# sensors.net
KiCad netlist of a schematic drawn in EAGLE
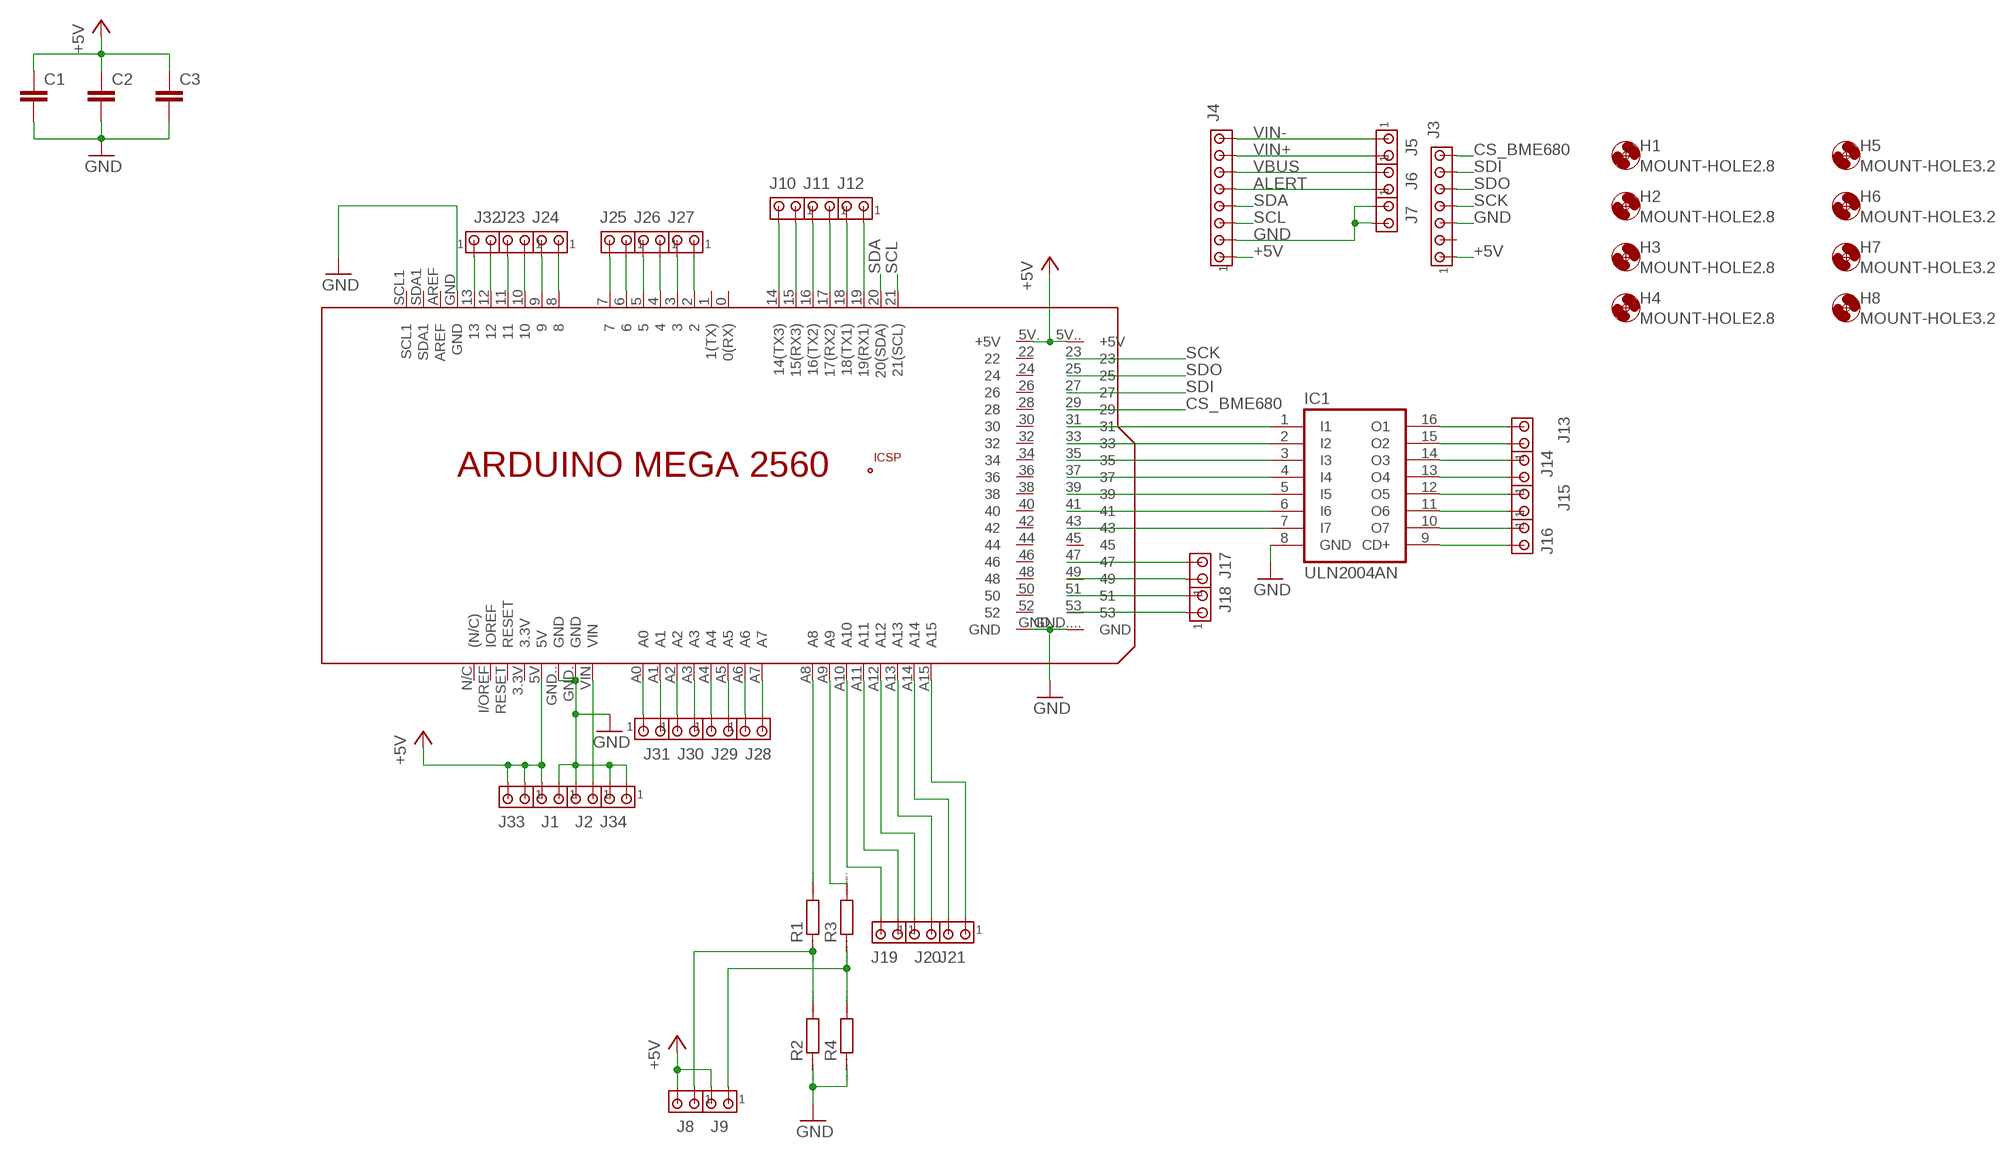
[diagram p0: schematic, sheet 1]

(export (version "E")
  (design (tool "Eeschema 10.0.6"))
  (components
    (comp (ref "C1")
      (value "C2,5-3")
      (footprint "eagle-import:C2.5-3")
      (libsource (lib "eagle-import") (part "C2,5-3"))
    )
    (comp (ref "C2")
      (value "C2,5-3")
      (footprint "eagle-import:C2.5-3")
      (libsource (lib "eagle-import") (part "C2,5-3"))
    )
    (comp (ref "C3")
      (value "C2,5-3")
      (footprint "eagle-import:C2.5-3")
      (libsource (lib "eagle-import") (part "C2,5-3"))
    )
    (comp (ref "H1")
      (value "MOUNT-HOLE2.8")
      (footprint "eagle-import:2,8")
      (libsource (lib "eagle-import") (part "MOUNT-HOLE2.8"))
    )
    (comp (ref "H2")
      (value "MOUNT-HOLE2.8")
      (footprint "eagle-import:2,8")
      (libsource (lib "eagle-import") (part "MOUNT-HOLE2.8"))
    )
    (comp (ref "H3")
      (value "MOUNT-HOLE2.8")
      (footprint "eagle-import:2,8")
      (libsource (lib "eagle-import") (part "MOUNT-HOLE2.8"))
    )
    (comp (ref "H4")
      (value "MOUNT-HOLE2.8")
      (footprint "eagle-import:2,8")
      (libsource (lib "eagle-import") (part "MOUNT-HOLE2.8"))
    )
    (comp (ref "H5")
      (value "MOUNT-HOLE3.2")
      (footprint "eagle-import:3,2")
      (libsource (lib "eagle-import") (part "MOUNT-HOLE3.2"))
    )
    (comp (ref "H6")
      (value "MOUNT-HOLE3.2")
      (footprint "eagle-import:3,2")
      (libsource (lib "eagle-import") (part "MOUNT-HOLE3.2"))
    )
    (comp (ref "H7")
      (value "MOUNT-HOLE3.2")
      (footprint "eagle-import:3,2")
      (libsource (lib "eagle-import") (part "MOUNT-HOLE3.2"))
    )
    (comp (ref "H8")
      (value "MOUNT-HOLE3.2")
      (footprint "eagle-import:3,2")
      (libsource (lib "eagle-import") (part "MOUNT-HOLE3.2"))
    )
    (comp (ref "IC1")
      (value "ULN2004AN")
      (footprint "eagle-import:DIL16")
      (libsource (lib "eagle-import") (part "ULN2004AN"))
    )
    (comp (ref "J1")
      (value "SCREW-2")
      (footprint "eagle-import:SCREW-2")
      (libsource (lib "eagle-import") (part "SCREW-2"))
    )
    (comp (ref "J2")
      (value "SCREW-2")
      (footprint "eagle-import:SCREW-2")
      (libsource (lib "eagle-import") (part "SCREW-2"))
    )
    (comp (ref "J3")
      (value "MTA07-100")
      (footprint "eagle-import:10X07MTA")
      (libsource (lib "eagle-import") (part "MTA07-100"))
    )
    (comp (ref "J4")
      (value "MTA08-100")
      (footprint "eagle-import:10X08MTA")
      (libsource (lib "eagle-import") (part "MTA08-100"))
    )
    (comp (ref "J5")
      (value "SCREW-2")
      (footprint "eagle-import:SCREW-2")
      (libsource (lib "eagle-import") (part "SCREW-2"))
    )
    (comp (ref "J6")
      (value "SCREW-2")
      (footprint "eagle-import:SCREW-2")
      (libsource (lib "eagle-import") (part "SCREW-2"))
    )
    (comp (ref "J7")
      (value "SCREW-2")
      (footprint "eagle-import:SCREW-2")
      (libsource (lib "eagle-import") (part "SCREW-2"))
    )
    (comp (ref "J8")
      (value "SCREW-2")
      (footprint "eagle-import:SCREW-2")
      (libsource (lib "eagle-import") (part "SCREW-2"))
    )
    (comp (ref "J9")
      (value "SCREW-2")
      (footprint "eagle-import:SCREW-2")
      (libsource (lib "eagle-import") (part "SCREW-2"))
    )
    (comp (ref "J10")
      (value "SCREW-2")
      (footprint "eagle-import:SCREW-2")
      (libsource (lib "eagle-import") (part "SCREW-2"))
    )
    (comp (ref "J11")
      (value "SCREW-2")
      (footprint "eagle-import:SCREW-2")
      (libsource (lib "eagle-import") (part "SCREW-2"))
    )
    (comp (ref "J12")
      (value "SCREW-2")
      (footprint "eagle-import:SCREW-2")
      (libsource (lib "eagle-import") (part "SCREW-2"))
    )
    (comp (ref "J13")
      (value "SCREW-2")
      (footprint "eagle-import:SCREW-2")
      (libsource (lib "eagle-import") (part "SCREW-2"))
    )
    (comp (ref "J14")
      (value "SCREW-2")
      (footprint "eagle-import:SCREW-2")
      (libsource (lib "eagle-import") (part "SCREW-2"))
    )
    (comp (ref "J15")
      (value "SCREW-2")
      (footprint "eagle-import:SCREW-2")
      (libsource (lib "eagle-import") (part "SCREW-2"))
    )
    (comp (ref "J16")
      (value "SCREW-2")
      (footprint "eagle-import:SCREW-2")
      (libsource (lib "eagle-import") (part "SCREW-2"))
    )
    (comp (ref "J17")
      (value "SCREW-2")
      (footprint "eagle-import:SCREW-2")
      (libsource (lib "eagle-import") (part "SCREW-2"))
    )
    (comp (ref "J18")
      (value "SCREW-2")
      (footprint "eagle-import:SCREW-2")
      (libsource (lib "eagle-import") (part "SCREW-2"))
    )
    (comp (ref "J19")
      (value "SCREW-2")
      (footprint "eagle-import:SCREW-2")
      (libsource (lib "eagle-import") (part "SCREW-2"))
    )
    (comp (ref "J20")
      (value "SCREW-2")
      (footprint "eagle-import:SCREW-2")
      (libsource (lib "eagle-import") (part "SCREW-2"))
    )
    (comp (ref "J21")
      (value "SCREW-2")
      (footprint "eagle-import:SCREW-2")
      (libsource (lib "eagle-import") (part "SCREW-2"))
    )
    (comp (ref "J23")
      (value "SCREW-2")
      (footprint "eagle-import:SCREW-2")
      (libsource (lib "eagle-import") (part "SCREW-2"))
    )
    (comp (ref "J24")
      (value "SCREW-2")
      (footprint "eagle-import:SCREW-2")
      (libsource (lib "eagle-import") (part "SCREW-2"))
    )
    (comp (ref "J25")
      (value "SCREW-2")
      (footprint "eagle-import:SCREW-2")
      (libsource (lib "eagle-import") (part "SCREW-2"))
    )
    (comp (ref "J26")
      (value "SCREW-2")
      (footprint "eagle-import:SCREW-2")
      (libsource (lib "eagle-import") (part "SCREW-2"))
    )
    (comp (ref "J27")
      (value "SCREW-2")
      (footprint "eagle-import:SCREW-2")
      (libsource (lib "eagle-import") (part "SCREW-2"))
    )
    (comp (ref "J28")
      (value "SCREW-2")
      (footprint "eagle-import:SCREW-2")
      (libsource (lib "eagle-import") (part "SCREW-2"))
    )
    (comp (ref "J29")
      (value "SCREW-2")
      (footprint "eagle-import:SCREW-2")
      (libsource (lib "eagle-import") (part "SCREW-2"))
    )
    (comp (ref "J30")
      (value "SCREW-2")
      (footprint "eagle-import:SCREW-2")
      (libsource (lib "eagle-import") (part "SCREW-2"))
    )
    (comp (ref "J31")
      (value "SCREW-2")
      (footprint "eagle-import:SCREW-2")
      (libsource (lib "eagle-import") (part "SCREW-2"))
    )
    (comp (ref "J32")
      (value "SCREW-2")
      (footprint "eagle-import:SCREW-2")
      (libsource (lib "eagle-import") (part "SCREW-2"))
    )
    (comp (ref "J33")
      (value "SCREW-2")
      (footprint "eagle-import:SCREW-2")
      (libsource (lib "eagle-import") (part "SCREW-2"))
    )
    (comp (ref "J34")
      (value "SCREW-2")
      (footprint "eagle-import:SCREW-2")
      (libsource (lib "eagle-import") (part "SCREW-2"))
    )
    (comp (ref "PCB1")
      (value "ARDUINO_MEGA2560_NEW")
      (footprint "eagle-import:ARDUINO_MEGA2560")
      (libsource (lib "eagle-import") (part "ARDUINO_MEGA2560_NEW"))
    )
    (comp (ref "R1")
      (value "R0207/10")
      (footprint "eagle-import:0207_10")
      (libsource (lib "eagle-import") (part "R0207/10"))
    )
    (comp (ref "R2")
      (value "R0207/10")
      (footprint "eagle-import:0207_10")
      (libsource (lib "eagle-import") (part "R0207/10"))
    )
    (comp (ref "R3")
      (value "R0207/10")
      (footprint "eagle-import:0207_10")
      (libsource (lib "eagle-import") (part "R0207/10"))
    )
    (comp (ref "R4")
      (value "R0207/10")
      (footprint "eagle-import:0207_10")
      (libsource (lib "eagle-import") (part "R0207/10"))
    )
  )
  (nets
    (net (code "1") (name "+5V") (class "Default")
      (node (ref "C1") (pin "1") (pinfunction "1_1") (pintype "passive"))
      (node (ref "C2") (pin "1") (pinfunction "1_1") (pintype "passive"))
      (node (ref "C3") (pin "1") (pinfunction "1_1") (pintype "passive"))
      (node (ref "J1") (pin "2") (pinfunction "2_2") (pintype "passive"))
      (node (ref "J3") (pin "1") (pinfunction "1_1") (pintype "passive"))
      (node (ref "J33") (pin "1") (pinfunction "1_1") (pintype "passive"))
      (node (ref "J33") (pin "2") (pinfunction "2_2") (pintype "passive"))
      (node (ref "J4") (pin "1") (pinfunction "1_1") (pintype "passive"))
      (node (ref "J8") (pin "2") (pinfunction "2_2") (pintype "passive"))
      (node (ref "J9") (pin "2") (pinfunction "2_2") (pintype "passive"))
      (node (ref "PCB1") (pin "5V") (pinfunction "5V_5V") (pintype "bidirectional"))
      (node (ref "PCB1") (pin "5V.") (pinfunction "+5V_5V.") (pintype "bidirectional"))
      (node (ref "PCB1") (pin "5V..") (pinfunction "+5V_5V..") (pintype "bidirectional"))
    )
    (net (code "2") (name "/ALERT") (class "Default")
      (node (ref "J4") (pin "5") (pinfunction "5_5") (pintype "passive"))
      (node (ref "J6") (pin "2") (pinfunction "2_2") (pintype "passive"))
    )
    (net (code "3") (name "/CS_BME680") (class "Default")
      (node (ref "J3") (pin "7") (pinfunction "7_7") (pintype "passive"))
      (node (ref "PCB1") (pin "29") (pinfunction "29_29") (pintype "bidirectional"))
    )
    (net (code "4") (name "/SCK") (class "Default")
      (node (ref "J3") (pin "4") (pinfunction "4_4") (pintype "passive"))
      (node (ref "PCB1") (pin "23") (pinfunction "23_23") (pintype "bidirectional"))
    )
    (net (code "5") (name "/SCL") (class "Default")
      (node (ref "J4") (pin "3") (pinfunction "3_3") (pintype "passive"))
      (node (ref "PCB1") (pin "21") (pinfunction "21(SCL)_21") (pintype "bidirectional"))
    )
    (net (code "6") (name "/SDA") (class "Default")
      (node (ref "J4") (pin "4") (pinfunction "4_4") (pintype "passive"))
      (node (ref "PCB1") (pin "20") (pinfunction "20(SDA)_20") (pintype "bidirectional"))
    )
    (net (code "7") (name "/SDI") (class "Default")
      (node (ref "J3") (pin "6") (pinfunction "6_6") (pintype "passive"))
      (node (ref "PCB1") (pin "27") (pinfunction "27_27") (pintype "bidirectional"))
    )
    (net (code "8") (name "/SDO") (class "Default")
      (node (ref "J3") (pin "5") (pinfunction "5_5") (pintype "passive"))
      (node (ref "PCB1") (pin "25") (pinfunction "25_25") (pintype "bidirectional"))
    )
    (net (code "9") (name "/VBUS") (class "Default")
      (node (ref "J4") (pin "6") (pinfunction "6_6") (pintype "passive"))
      (node (ref "J6") (pin "1") (pinfunction "1_1") (pintype "passive"))
    )
    (net (code "10") (name "/VIN+") (class "Default")
      (node (ref "J4") (pin "7") (pinfunction "7_7") (pintype "passive"))
      (node (ref "J5") (pin "2") (pinfunction "2_2") (pintype "passive"))
    )
    (net (code "11") (name "/VIN-") (class "Default")
      (node (ref "J4") (pin "8") (pinfunction "8_8") (pintype "passive"))
      (node (ref "J5") (pin "1") (pinfunction "1_1") (pintype "passive"))
    )
    (net (code "12") (name "GND") (class "Default")
      (node (ref "C1") (pin "2") (pinfunction "2_2") (pintype "passive"))
      (node (ref "C2") (pin "2") (pinfunction "2_2") (pintype "passive"))
      (node (ref "C3") (pin "2") (pinfunction "2_2") (pintype "passive"))
      (node (ref "IC1") (pin "8") (pinfunction "GND_8") (pintype "power_in"))
      (node (ref "J1") (pin "1") (pinfunction "1_1") (pintype "passive"))
      (node (ref "J2") (pin "2") (pinfunction "2_2") (pintype "passive"))
      (node (ref "J3") (pin "3") (pinfunction "3_3") (pintype "passive"))
      (node (ref "J34") (pin "1") (pinfunction "1_1") (pintype "passive"))
      (node (ref "J34") (pin "2") (pinfunction "2_2") (pintype "passive"))
      (node (ref "J4") (pin "2") (pinfunction "2_2") (pintype "passive"))
      (node (ref "J7") (pin "1") (pinfunction "1_1") (pintype "passive"))
      (node (ref "J7") (pin "2") (pinfunction "2_2") (pintype "passive"))
      (node (ref "PCB1") (pin "GND") (pinfunction "GND_GND") (pintype "bidirectional"))
      (node (ref "PCB1") (pin "GND.") (pinfunction "GND_GND.") (pintype "bidirectional"))
      (node (ref "PCB1") (pin "GND..") (pinfunction "GND_GND..") (pintype "bidirectional"))
      (node (ref "PCB1") (pin "GND...") (pinfunction "GND_GND...") (pintype "bidirectional"))
      (node (ref "PCB1") (pin "GND....") (pinfunction "GND_GND....") (pintype "bidirectional"))
      (node (ref "R2") (pin "1") (pinfunction "1_1") (pintype "passive"))
      (node (ref "R4") (pin "1") (pinfunction "1_1") (pintype "passive"))
    )
    (net (code "13") (name "Net-(IC1-CD+)") (class "Default")
      (node (ref "IC1") (pin "9") (pinfunction "CD+_9") (pintype "passive"))
      (node (ref "J16") (pin "2") (pinfunction "2_2") (pintype "passive"))
    )
    (net (code "14") (name "Net-(IC1-I1)") (class "Default")
      (node (ref "IC1") (pin "1") (pinfunction "I1_1") (pintype "input"))
      (node (ref "PCB1") (pin "31") (pinfunction "31_31") (pintype "bidirectional"))
    )
    (net (code "15") (name "Net-(IC1-I2)") (class "Default")
      (node (ref "IC1") (pin "2") (pinfunction "I2_2") (pintype "input"))
      (node (ref "PCB1") (pin "33") (pinfunction "33_33") (pintype "bidirectional"))
    )
    (net (code "16") (name "Net-(IC1-I3)") (class "Default")
      (node (ref "IC1") (pin "3") (pinfunction "I3_3") (pintype "input"))
      (node (ref "PCB1") (pin "35") (pinfunction "35_35") (pintype "bidirectional"))
    )
    (net (code "17") (name "Net-(IC1-I4)") (class "Default")
      (node (ref "IC1") (pin "4") (pinfunction "I4_4") (pintype "input"))
      (node (ref "PCB1") (pin "37") (pinfunction "37_37") (pintype "bidirectional"))
    )
    (net (code "18") (name "Net-(IC1-I5)") (class "Default")
      (node (ref "IC1") (pin "5") (pinfunction "I5_5") (pintype "input"))
      (node (ref "PCB1") (pin "39") (pinfunction "39_39") (pintype "bidirectional"))
    )
    (net (code "19") (name "Net-(IC1-I6)") (class "Default")
      (node (ref "IC1") (pin "6") (pinfunction "I6_6") (pintype "input"))
      (node (ref "PCB1") (pin "41") (pinfunction "41_41") (pintype "bidirectional"))
    )
    (net (code "20") (name "Net-(IC1-I7)") (class "Default")
      (node (ref "IC1") (pin "7") (pinfunction "I7_7") (pintype "input"))
      (node (ref "PCB1") (pin "43") (pinfunction "43_43") (pintype "bidirectional"))
    )
    (net (code "21") (name "Net-(IC1-O1)") (class "Default")
      (node (ref "IC1") (pin "16") (pinfunction "O1_16") (pintype "open_collector"))
      (node (ref "J13") (pin "2") (pinfunction "2_2") (pintype "passive"))
    )
    (net (code "22") (name "Net-(IC1-O2)") (class "Default")
      (node (ref "IC1") (pin "15") (pinfunction "O2_15") (pintype "open_collector"))
      (node (ref "J13") (pin "1") (pinfunction "1_1") (pintype "passive"))
    )
    (net (code "23") (name "Net-(IC1-O3)") (class "Default")
      (node (ref "IC1") (pin "14") (pinfunction "O3_14") (pintype "open_collector"))
      (node (ref "J14") (pin "2") (pinfunction "2_2") (pintype "passive"))
    )
    (net (code "24") (name "Net-(IC1-O4)") (class "Default")
      (node (ref "IC1") (pin "13") (pinfunction "O4_13") (pintype "open_collector"))
      (node (ref "J14") (pin "1") (pinfunction "1_1") (pintype "passive"))
    )
    (net (code "25") (name "Net-(IC1-O5)") (class "Default")
      (node (ref "IC1") (pin "12") (pinfunction "O5_12") (pintype "open_collector"))
      (node (ref "J15") (pin "2") (pinfunction "2_2") (pintype "passive"))
    )
    (net (code "26") (name "Net-(IC1-O6)") (class "Default")
      (node (ref "IC1") (pin "11") (pinfunction "O6_11") (pintype "open_collector"))
      (node (ref "J15") (pin "1") (pinfunction "1_1") (pintype "passive"))
    )
    (net (code "27") (name "Net-(IC1-O7)") (class "Default")
      (node (ref "IC1") (pin "10") (pinfunction "O7_10") (pintype "open_collector"))
      (node (ref "J16") (pin "1") (pinfunction "1_1") (pintype "passive"))
    )
    (net (code "28") (name "Net-(J2-Pad1)") (class "Default")
      (node (ref "J2") (pin "1") (pinfunction "1_1") (pintype "passive"))
      (node (ref "PCB1") (pin "VIN") (pinfunction "VIN_VIN") (pintype "bidirectional"))
    )
    (net (code "29") (name "Net-(J8-Pad1)") (class "Default")
      (node (ref "J8") (pin "1") (pinfunction "1_1") (pintype "passive"))
      (node (ref "R1") (pin "1") (pinfunction "1_1") (pintype "passive"))
      (node (ref "R2") (pin "2") (pinfunction "2_2") (pintype "passive"))
    )
    (net (code "30") (name "Net-(J9-Pad1)") (class "Default")
      (node (ref "J9") (pin "1") (pinfunction "1_1") (pintype "passive"))
      (node (ref "R3") (pin "1") (pinfunction "1_1") (pintype "passive"))
      (node (ref "R4") (pin "2") (pinfunction "2_2") (pintype "passive"))
    )
    (net (code "31") (name "Net-(J17-Pad1)") (class "Default")
      (node (ref "J17") (pin "1") (pinfunction "1_1") (pintype "passive"))
      (node (ref "PCB1") (pin "49") (pinfunction "49_49") (pintype "bidirectional"))
    )
    (net (code "32") (name "Net-(J17-Pad2)") (class "Default")
      (node (ref "J17") (pin "2") (pinfunction "2_2") (pintype "passive"))
      (node (ref "PCB1") (pin "47") (pinfunction "47_47") (pintype "bidirectional"))
    )
    (net (code "33") (name "Net-(J18-Pad1)") (class "Default")
      (node (ref "J18") (pin "1") (pinfunction "1_1") (pintype "passive"))
      (node (ref "PCB1") (pin "53") (pinfunction "53_53") (pintype "bidirectional"))
    )
    (net (code "34") (name "Net-(J18-Pad2)") (class "Default")
      (node (ref "J18") (pin "2") (pinfunction "2_2") (pintype "passive"))
      (node (ref "PCB1") (pin "51") (pinfunction "51_51") (pintype "bidirectional"))
    )
    (net (code "35") (name "Net-(J19-Pad1)") (class "Default")
      (node (ref "J19") (pin "1") (pinfunction "1_1") (pintype "passive"))
      (node (ref "PCB1") (pin "A11") (pinfunction "A11_A11") (pintype "bidirectional"))
    )
    (net (code "36") (name "Net-(J19-Pad2)") (class "Default")
      (node (ref "J19") (pin "2") (pinfunction "2_2") (pintype "passive"))
      (node (ref "PCB1") (pin "A10") (pinfunction "A10_A10") (pintype "bidirectional"))
    )
    (net (code "37") (name "Net-(J20-Pad1)") (class "Default")
      (node (ref "J20") (pin "1") (pinfunction "1_1") (pintype "passive"))
      (node (ref "PCB1") (pin "A12") (pinfunction "A12_A12") (pintype "bidirectional"))
    )
    (net (code "38") (name "Net-(J20-Pad2)") (class "Default")
      (node (ref "J20") (pin "2") (pinfunction "2_2") (pintype "passive"))
      (node (ref "PCB1") (pin "A13") (pinfunction "A13_A13") (pintype "bidirectional"))
    )
    (net (code "39") (name "Net-(J21-Pad1)") (class "Default")
      (node (ref "J21") (pin "1") (pinfunction "1_1") (pintype "passive"))
      (node (ref "PCB1") (pin "A15") (pinfunction "A15_A15") (pintype "bidirectional"))
    )
    (net (code "40") (name "Net-(J21-Pad2)") (class "Default")
      (node (ref "J21") (pin "2") (pinfunction "2_2") (pintype "passive"))
      (node (ref "PCB1") (pin "A14") (pinfunction "A14_A14") (pintype "bidirectional"))
    )
    (net (code "41") (name "Net-(J23-Pad1)") (class "Default")
      (node (ref "J23") (pin "1") (pinfunction "1_1") (pintype "passive"))
      (node (ref "PCB1") (pin "10") (pinfunction "10_10") (pintype "bidirectional"))
    )
    (net (code "42") (name "Net-(J23-Pad2)") (class "Default")
      (node (ref "J23") (pin "2") (pinfunction "2_2") (pintype "passive"))
      (node (ref "PCB1") (pin "11") (pinfunction "11_11") (pintype "bidirectional"))
    )
    (net (code "43") (name "Net-(J24-Pad1)") (class "Default")
      (node (ref "J24") (pin "1") (pinfunction "1_1") (pintype "passive"))
      (node (ref "PCB1") (pin "8") (pinfunction "8_8") (pintype "bidirectional"))
    )
    (net (code "44") (name "Net-(J24-Pad2)") (class "Default")
      (node (ref "J24") (pin "2") (pinfunction "2_2") (pintype "passive"))
      (node (ref "PCB1") (pin "9") (pinfunction "9_9") (pintype "bidirectional"))
    )
    (net (code "45") (name "Net-(J25-Pad1)") (class "Default")
      (node (ref "J25") (pin "1") (pinfunction "1_1") (pintype "passive"))
      (node (ref "PCB1") (pin "6") (pinfunction "6_6") (pintype "bidirectional"))
    )
    (net (code "46") (name "Net-(J25-Pad2)") (class "Default")
      (node (ref "J25") (pin "2") (pinfunction "2_2") (pintype "passive"))
      (node (ref "PCB1") (pin "7") (pinfunction "7_7") (pintype "bidirectional"))
    )
    (net (code "47") (name "Net-(J26-Pad1)") (class "Default")
      (node (ref "J26") (pin "1") (pinfunction "1_1") (pintype "passive"))
      (node (ref "PCB1") (pin "4") (pinfunction "4_4") (pintype "bidirectional"))
    )
    (net (code "48") (name "Net-(J26-Pad2)") (class "Default")
      (node (ref "J26") (pin "2") (pinfunction "2_2") (pintype "passive"))
      (node (ref "PCB1") (pin "5") (pinfunction "5_5") (pintype "bidirectional"))
    )
    (net (code "49") (name "Net-(J27-Pad1)") (class "Default")
      (node (ref "J27") (pin "1") (pinfunction "1_1") (pintype "passive"))
      (node (ref "PCB1") (pin "2") (pinfunction "2_2") (pintype "bidirectional"))
    )
    (net (code "50") (name "Net-(J27-Pad2)") (class "Default")
      (node (ref "J27") (pin "2") (pinfunction "2_2") (pintype "passive"))
      (node (ref "PCB1") (pin "3") (pinfunction "3_3") (pintype "bidirectional"))
    )
    (net (code "51") (name "Net-(J28-Pad1)") (class "Default")
      (node (ref "J28") (pin "1") (pinfunction "1_1") (pintype "passive"))
      (node (ref "PCB1") (pin "A6") (pinfunction "A6_A6") (pintype "bidirectional"))
    )
    (net (code "52") (name "Net-(J28-Pad2)") (class "Default")
      (node (ref "J28") (pin "2") (pinfunction "2_2") (pintype "passive"))
      (node (ref "PCB1") (pin "A7") (pinfunction "A7_A7") (pintype "bidirectional"))
    )
    (net (code "53") (name "Net-(J29-Pad1)") (class "Default")
      (node (ref "J29") (pin "1") (pinfunction "1_1") (pintype "passive"))
      (node (ref "PCB1") (pin "A4") (pinfunction "A4_A4") (pintype "bidirectional"))
    )
    (net (code "54") (name "Net-(J29-Pad2)") (class "Default")
      (node (ref "J29") (pin "2") (pinfunction "2_2") (pintype "passive"))
      (node (ref "PCB1") (pin "A5") (pinfunction "A5_A5") (pintype "bidirectional"))
    )
    (net (code "55") (name "Net-(J30-Pad1)") (class "Default")
      (node (ref "J30") (pin "1") (pinfunction "1_1") (pintype "passive"))
      (node (ref "PCB1") (pin "A2") (pinfunction "A2_A2") (pintype "bidirectional"))
    )
    (net (code "56") (name "Net-(J30-Pad2)") (class "Default")
      (node (ref "J30") (pin "2") (pinfunction "2_2") (pintype "passive"))
      (node (ref "PCB1") (pin "A3") (pinfunction "A3_A3") (pintype "bidirectional"))
    )
    (net (code "57") (name "Net-(J31-Pad1)") (class "Default")
      (node (ref "J31") (pin "1") (pinfunction "1_1") (pintype "passive"))
      (node (ref "PCB1") (pin "A0") (pinfunction "A0_A0") (pintype "bidirectional"))
    )
    (net (code "58") (name "Net-(J31-Pad2)") (class "Default")
      (node (ref "J31") (pin "2") (pinfunction "2_2") (pintype "passive"))
      (node (ref "PCB1") (pin "A1") (pinfunction "A1_A1") (pintype "bidirectional"))
    )
    (net (code "59") (name "Net-(J32-Pad1)") (class "Default")
      (node (ref "J32") (pin "1") (pinfunction "1_1") (pintype "passive"))
      (node (ref "PCB1") (pin "13") (pinfunction "13_13") (pintype "bidirectional"))
    )
    (net (code "60") (name "Net-(J32-Pad2)") (class "Default")
      (node (ref "J32") (pin "2") (pinfunction "2_2") (pintype "passive"))
      (node (ref "PCB1") (pin "12") (pinfunction "12_12") (pintype "bidirectional"))
    )
    (net (code "61") (name "Net-(PCB1-14(TX3))") (class "Default")
      (node (ref "J10") (pin "2") (pinfunction "2_2") (pintype "passive"))
      (node (ref "PCB1") (pin "14") (pinfunction "14(TX3)_14") (pintype "bidirectional"))
    )
    (net (code "62") (name "Net-(PCB1-15(RX3))") (class "Default")
      (node (ref "J10") (pin "1") (pinfunction "1_1") (pintype "passive"))
      (node (ref "PCB1") (pin "15") (pinfunction "15(RX3)_15") (pintype "bidirectional"))
    )
    (net (code "63") (name "Net-(PCB1-16(TX2))") (class "Default")
      (node (ref "J11") (pin "2") (pinfunction "2_2") (pintype "passive"))
      (node (ref "PCB1") (pin "16") (pinfunction "16(TX2)_16") (pintype "bidirectional"))
    )
    (net (code "64") (name "Net-(PCB1-17(RX2))") (class "Default")
      (node (ref "J11") (pin "1") (pinfunction "1_1") (pintype "passive"))
      (node (ref "PCB1") (pin "17") (pinfunction "17(RX2)_17") (pintype "bidirectional"))
    )
    (net (code "65") (name "Net-(PCB1-18(TX1))") (class "Default")
      (node (ref "J12") (pin "2") (pinfunction "2_2") (pintype "passive"))
      (node (ref "PCB1") (pin "18") (pinfunction "18(TX1)_18") (pintype "bidirectional"))
    )
    (net (code "66") (name "Net-(PCB1-19(RX1))") (class "Default")
      (node (ref "J12") (pin "1") (pinfunction "1_1") (pintype "passive"))
      (node (ref "PCB1") (pin "19") (pinfunction "19(RX1)_19") (pintype "bidirectional"))
    )
    (net (code "67") (name "Net-(PCB1-PadA8)") (class "Default")
      (node (ref "PCB1") (pin "A8") (pinfunction "A8_A8") (pintype "bidirectional"))
      (node (ref "R1") (pin "2") (pinfunction "2_2") (pintype "passive"))
    )
    (net (code "68") (name "Net-(PCB1-PadA9)") (class "Default")
      (node (ref "PCB1") (pin "A9") (pinfunction "A9_A9") (pintype "bidirectional"))
      (node (ref "R3") (pin "2") (pinfunction "2_2") (pintype "passive"))
    )
    (net (code "69") (name "unconnected-(J3-Pad2)") (class "Default")
      (node (ref "J3") (pin "2") (pinfunction "2_2") (pintype "passive"))
    )
    (net (code "70") (name "unconnected-(PCB1-(N{slash}C)-PadN{slash}C)") (class "Default")
      (node (ref "PCB1") (pin "N/C") (pinfunction "(N/C)_N/C") (pintype "bidirectional"))
    )
    (net (code "71") (name "unconnected-(PCB1-0(RX)-Pad0)") (class "Default")
      (node (ref "PCB1") (pin "0") (pinfunction "0(RX)_0") (pintype "bidirectional"))
    )
    (net (code "72") (name "unconnected-(PCB1-1(TX)-Pad1)") (class "Default")
      (node (ref "PCB1") (pin "1") (pinfunction "1(TX)_1") (pintype "bidirectional"))
    )
    (net (code "73") (name "unconnected-(PCB1-IOREF-PadI{slash}OREF)") (class "Default")
      (node (ref "PCB1") (pin "I/OREF") (pinfunction "IOREF_I/OREF") (pintype "bidirectional"))
    )
    (net (code "74") (name "unconnected-(PCB1-Pad+5V_)") (class "Default")
      (node (ref "PCB1") (pin "+5V_") (pinfunction "+5V__+5V_") (pintype "bidirectional"))
    )
    (net (code "75") (name "unconnected-(PCB1-Pad3.3V)") (class "Default")
      (node (ref "PCB1") (pin "3.3V") (pinfunction "3.3V_3.3V") (pintype "bidirectional"))
    )
    (net (code "76") (name "unconnected-(PCB1-Pad22)") (class "Default")
      (node (ref "PCB1") (pin "22") (pinfunction "22_22") (pintype "bidirectional"))
    )
    (net (code "77") (name "unconnected-(PCB1-Pad24)") (class "Default")
      (node (ref "PCB1") (pin "24") (pinfunction "24_24") (pintype "bidirectional"))
    )
    (net (code "78") (name "unconnected-(PCB1-Pad26)") (class "Default")
      (node (ref "PCB1") (pin "26") (pinfunction "26_26") (pintype "bidirectional"))
    )
    (net (code "79") (name "unconnected-(PCB1-Pad28)") (class "Default")
      (node (ref "PCB1") (pin "28") (pinfunction "28_28") (pintype "bidirectional"))
    )
    (net (code "80") (name "unconnected-(PCB1-Pad30)") (class "Default")
      (node (ref "PCB1") (pin "30") (pinfunction "30_30") (pintype "bidirectional"))
    )
    (net (code "81") (name "unconnected-(PCB1-Pad32)") (class "Default")
      (node (ref "PCB1") (pin "32") (pinfunction "32_32") (pintype "bidirectional"))
    )
    (net (code "82") (name "unconnected-(PCB1-Pad34)") (class "Default")
      (node (ref "PCB1") (pin "34") (pinfunction "34_34") (pintype "bidirectional"))
    )
    (net (code "83") (name "unconnected-(PCB1-Pad36)") (class "Default")
      (node (ref "PCB1") (pin "36") (pinfunction "36_36") (pintype "bidirectional"))
    )
    (net (code "84") (name "unconnected-(PCB1-Pad38)") (class "Default")
      (node (ref "PCB1") (pin "38") (pinfunction "38_38") (pintype "bidirectional"))
    )
    (net (code "85") (name "unconnected-(PCB1-Pad40)") (class "Default")
      (node (ref "PCB1") (pin "40") (pinfunction "40_40") (pintype "bidirectional"))
    )
    (net (code "86") (name "unconnected-(PCB1-Pad42)") (class "Default")
      (node (ref "PCB1") (pin "42") (pinfunction "42_42") (pintype "bidirectional"))
    )
    (net (code "87") (name "unconnected-(PCB1-Pad44)") (class "Default")
      (node (ref "PCB1") (pin "44") (pinfunction "44_44") (pintype "bidirectional"))
    )
    (net (code "88") (name "unconnected-(PCB1-Pad45)") (class "Default")
      (node (ref "PCB1") (pin "45") (pinfunction "45_45") (pintype "bidirectional"))
    )
    (net (code "89") (name "unconnected-(PCB1-Pad46)") (class "Default")
      (node (ref "PCB1") (pin "46") (pinfunction "46_46") (pintype "bidirectional"))
    )
    (net (code "90") (name "unconnected-(PCB1-Pad48)") (class "Default")
      (node (ref "PCB1") (pin "48") (pinfunction "48_48") (pintype "bidirectional"))
    )
    (net (code "91") (name "unconnected-(PCB1-Pad50)") (class "Default")
      (node (ref "PCB1") (pin "50") (pinfunction "50_50") (pintype "bidirectional"))
    )
    (net (code "92") (name "unconnected-(PCB1-Pad52)") (class "Default")
      (node (ref "PCB1") (pin "52") (pinfunction "52_52") (pintype "bidirectional"))
    )
    (net (code "93") (name "unconnected-(PCB1-PadAREF)") (class "Default")
      (node (ref "PCB1") (pin "AREF") (pinfunction "AREF_AREF") (pintype "bidirectional"))
    )
    (net (code "94") (name "unconnected-(PCB1-PadGND__)") (class "Default")
      (node (ref "PCB1") (pin "GND__") (pinfunction "GND___GND__") (pintype "bidirectional"))
    )
    (net (code "95") (name "unconnected-(PCB1-PadMISO)") (class "Default")
      (node (ref "PCB1") (pin "MISO") (pinfunction "MISO_MISO") (pintype "bidirectional"))
    )
    (net (code "96") (name "unconnected-(PCB1-PadMOSI)") (class "Default")
      (node (ref "PCB1") (pin "MOSI") (pinfunction "MOSI_MOSI") (pintype "bidirectional"))
    )
    (net (code "97") (name "unconnected-(PCB1-PadRESET)") (class "Default")
      (node (ref "PCB1") (pin "RESET") (pinfunction "RESET_RESET") (pintype "bidirectional"))
    )
    (net (code "98") (name "unconnected-(PCB1-PadRESET.)") (class "Default")
      (node (ref "PCB1") (pin "RESET.") (pinfunction "RESET._RESET.") (pintype "bidirectional"))
    )
    (net (code "99") (name "unconnected-(PCB1-PadSCK)") (class "Default")
      (node (ref "PCB1") (pin "SCK") (pinfunction "SCK_SCK") (pintype "bidirectional"))
    )
    (net (code "100") (name "unconnected-(PCB1-PadSCL1)") (class "Default")
      (node (ref "PCB1") (pin "SCL1") (pinfunction "SCL1_SCL1") (pintype "bidirectional"))
    )
    (net (code "101") (name "unconnected-(PCB1-PadSDA1)") (class "Default")
      (node (ref "PCB1") (pin "SDA1") (pinfunction "SDA1_SDA1") (pintype "bidirectional"))
    )
  )
)
